# 09_Zynq_DDR.net
KiCad netlist of a schematic drawn in Altium Designer
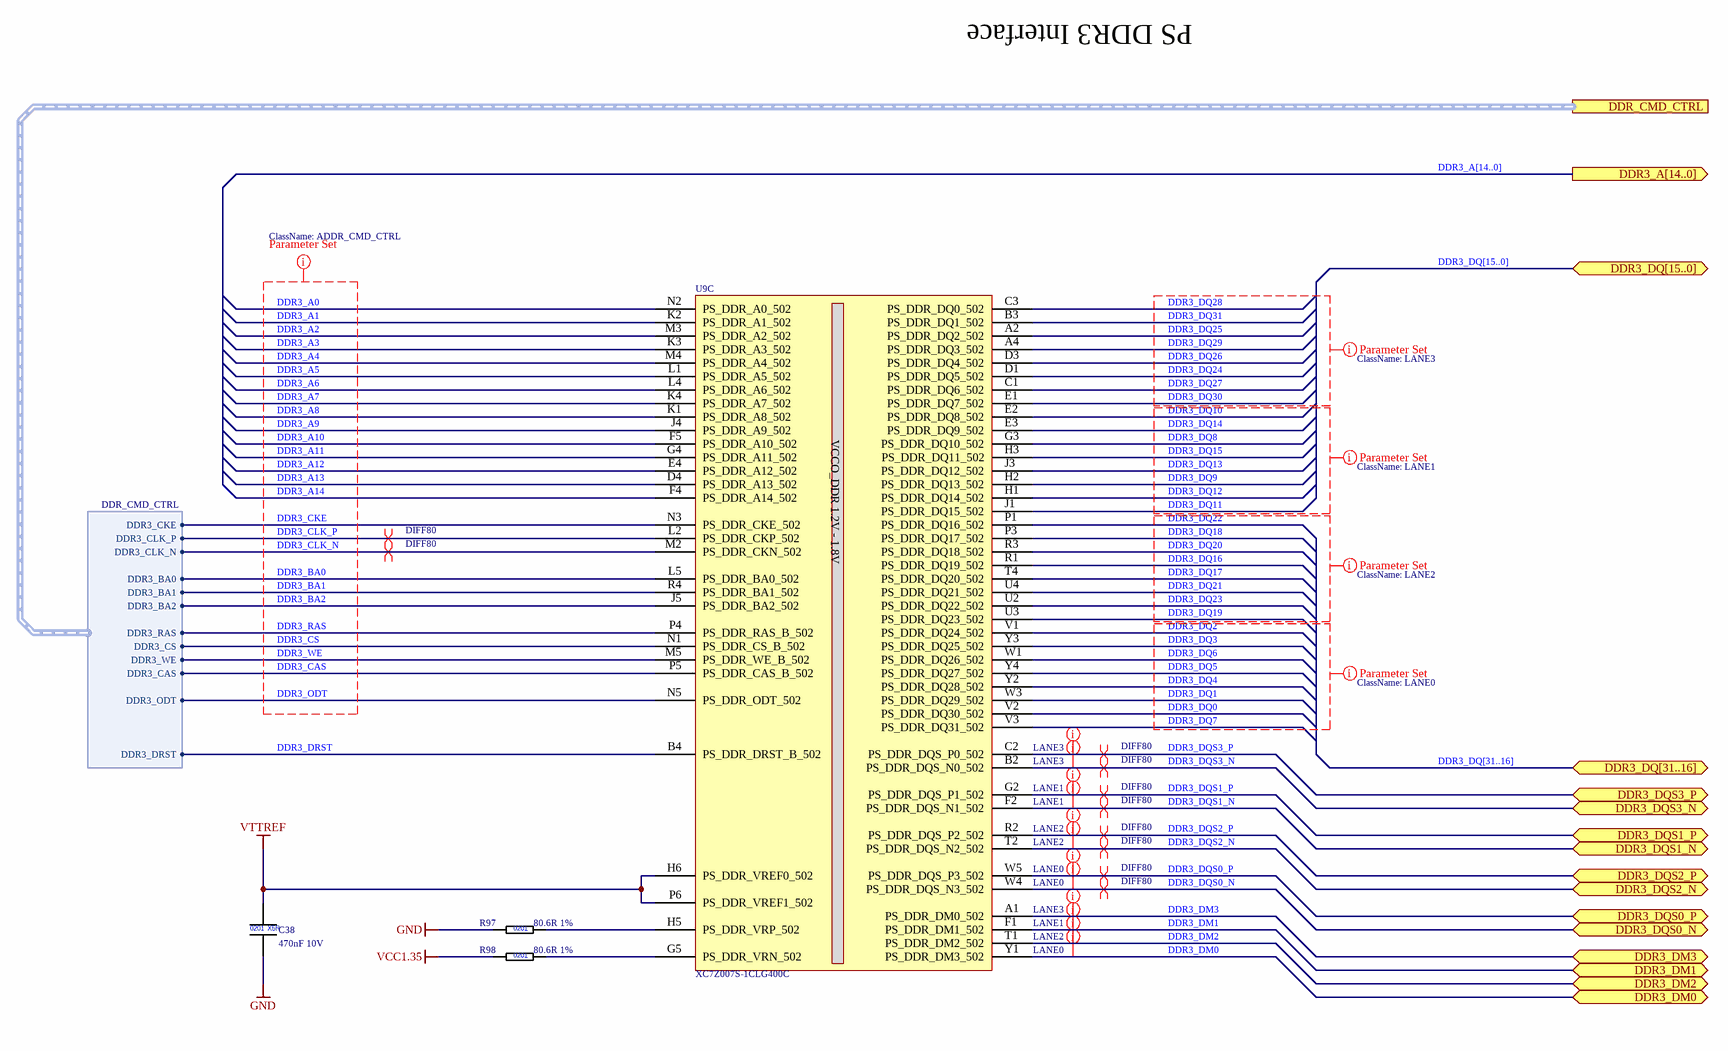
[diagram p0: 09_Zynq DDR.SchDoc]

(export (version "E")
  (design (tool "Eeschema 10.0.6"))
  (components
    (comp (ref "C38")
      (value "470nF 10V")
      (footprint "Zynq-Feather-HD:CAPC0603X03L")
      (description "Multilayer Ceramic Capacitors MLCC - SMD/SMT 0201 10VDC")
      (libsource (lib "Zynq-Feather-HD") (part "CAP_0201_470nF_10V"))
    )
    (comp (ref "R97")
      (value "80.6R 1%")
      (footprint "Zynq-Feather-HD:RESC0603X03L")
      (description "Thick Film Resistors - SMD 80.6R OHM 1%")
      (libsource (lib "Zynq-Feather-HD") (part "RES_0201_80.6R_1%"))
    )
    (comp (ref "R98")
      (value "80.6R 1%")
      (footprint "Zynq-Feather-HD:RESC0603X03L")
      (description "Thick Film Resistors - SMD 80.6R OHM 1%")
      (libsource (lib "Zynq-Feather-HD") (part "RES_0201_80.6R_1%"))
    )
    (comp (ref "U9")
      (value "XC7Z007S-1CLG400C")
      (footprint "Zynq-Feather-HD:BGA400C80P20X20_1700X1700X160")
      (description "XC7Z007S-1CLG400C_Processors - Application Specialised")
      (libsource (lib "Zynq-Feather-HD") (part "XC7Z007S-1CLG400C_Processors - Application Specialised"))
    )
  )
  (nets
    (net (code "2") (name "/DDR3_A0") (class "Default")
      (node (ref "U9") (pin "N2") (pinfunction "PS_DDR_A0_502_N2") (pintype "passive"))
    )
    (net (code "3") (name "/DDR3_A1") (class "Default")
      (node (ref "U9") (pin "K2") (pinfunction "PS_DDR_A1_502_K2") (pintype "passive"))
    )
    (net (code "4") (name "/DDR3_A2") (class "Default")
      (node (ref "U9") (pin "M3") (pinfunction "PS_DDR_A2_502_M3") (pintype "passive"))
    )
    (net (code "5") (name "/DDR3_A3") (class "Default")
      (node (ref "U9") (pin "K3") (pinfunction "PS_DDR_A3_502_K3") (pintype "passive"))
    )
    (net (code "6") (name "/DDR3_A4") (class "Default")
      (node (ref "U9") (pin "M4") (pinfunction "PS_DDR_A4_502_M4") (pintype "passive"))
    )
    (net (code "7") (name "/DDR3_A5") (class "Default")
      (node (ref "U9") (pin "L1") (pinfunction "PS_DDR_A5_502_L1") (pintype "passive"))
    )
    (net (code "8") (name "/DDR3_A6") (class "Default")
      (node (ref "U9") (pin "L4") (pinfunction "PS_DDR_A6_502_L4") (pintype "passive"))
    )
    (net (code "9") (name "/DDR3_A7") (class "Default")
      (node (ref "U9") (pin "K4") (pinfunction "PS_DDR_A7_502_K4") (pintype "passive"))
    )
    (net (code "10") (name "/DDR3_A8") (class "Default")
      (node (ref "U9") (pin "K1") (pinfunction "PS_DDR_A8_502_K1") (pintype "passive"))
    )
    (net (code "11") (name "/DDR3_A9") (class "Default")
      (node (ref "U9") (pin "J4") (pinfunction "PS_DDR_A9_502_J4") (pintype "passive"))
    )
    (net (code "12") (name "/DDR3_A10") (class "Default")
      (node (ref "U9") (pin "F5") (pinfunction "PS_DDR_A10_502_F5") (pintype "passive"))
    )
    (net (code "13") (name "/DDR3_A11") (class "Default")
      (node (ref "U9") (pin "G4") (pinfunction "PS_DDR_A11_502_G4") (pintype "passive"))
    )
    (net (code "14") (name "/DDR3_A12") (class "Default")
      (node (ref "U9") (pin "E4") (pinfunction "PS_DDR_A12_502_E4") (pintype "passive"))
    )
    (net (code "15") (name "/DDR3_A13") (class "Default")
      (node (ref "U9") (pin "D4") (pinfunction "PS_DDR_A13_502_D4") (pintype "passive"))
    )
    (net (code "16") (name "/DDR3_A14") (class "Default")
      (node (ref "U9") (pin "F4") (pinfunction "PS_DDR_A14_502_F4") (pintype "passive"))
    )
    (net (code "18") (name "/DDR3_BA0") (class "Default")
      (node (ref "U9") (pin "L5") (pinfunction "PS_DDR_BA0_502_L5") (pintype "passive"))
    )
    (net (code "19") (name "/DDR3_BA1") (class "Default")
      (node (ref "U9") (pin "R4") (pinfunction "PS_DDR_BA1_502_R4") (pintype "passive"))
    )
    (net (code "20") (name "/DDR3_BA2") (class "Default")
      (node (ref "U9") (pin "J5") (pinfunction "PS_DDR_BA2_502_J5") (pintype "passive"))
    )
    (net (code "21") (name "/DDR3_CAS") (class "Default")
      (node (ref "U9") (pin "P5") (pinfunction "PS_DDR_CAS_B_502_P5") (pintype "passive"))
    )
    (net (code "22") (name "/DDR3_CKE") (class "Default")
      (node (ref "U9") (pin "N3") (pinfunction "PS_DDR_CKE_502_N3") (pintype "passive"))
    )
    (net (code "23") (name "/DDR3_CLK_N") (class "Default")
      (node (ref "U9") (pin "M2") (pinfunction "PS_DDR_CKN_502_M2") (pintype "passive"))
    )
    (net (code "24") (name "/DDR3_CLK_P") (class "Default")
      (node (ref "U9") (pin "L2") (pinfunction "PS_DDR_CKP_502_L2") (pintype "passive"))
    )
    (net (code "25") (name "/DDR3_CS") (class "Default")
      (node (ref "U9") (pin "N1") (pinfunction "PS_DDR_CS_B_502_N1") (pintype "passive"))
    )
    (net (code "26") (name "/DDR3_DM0") (class "Default")
      (node (ref "U9") (pin "Y1") (pinfunction "PS_DDR_DM3_502_Y1") (pintype "passive"))
    )
    (net (code "27") (name "/DDR3_DM1") (class "Default")
      (node (ref "U9") (pin "F1") (pinfunction "PS_DDR_DM1_502_F1") (pintype "passive"))
    )
    (net (code "28") (name "/DDR3_DM2") (class "Default")
      (node (ref "U9") (pin "T1") (pinfunction "PS_DDR_DM2_502_T1") (pintype "passive"))
    )
    (net (code "29") (name "/DDR3_DM3") (class "Default")
      (node (ref "U9") (pin "A1") (pinfunction "PS_DDR_DM0_502_A1") (pintype "passive"))
    )
    (net (code "30") (name "/DDR3_DQ0") (class "Default")
      (node (ref "U9") (pin "V2") (pinfunction "PS_DDR_DQ30_502_V2") (pintype "passive"))
    )
    (net (code "31") (name "/DDR3_DQ1") (class "Default")
      (node (ref "U9") (pin "W3") (pinfunction "PS_DDR_DQ29_502_W3") (pintype "passive"))
    )
    (net (code "32") (name "/DDR3_DQ2") (class "Default")
      (node (ref "U9") (pin "V1") (pinfunction "PS_DDR_DQ24_502_V1") (pintype "passive"))
    )
    (net (code "33") (name "/DDR3_DQ3") (class "Default")
      (node (ref "U9") (pin "Y3") (pinfunction "PS_DDR_DQ25_502_Y3") (pintype "passive"))
    )
    (net (code "34") (name "/DDR3_DQ4") (class "Default")
      (node (ref "U9") (pin "Y2") (pinfunction "PS_DDR_DQ28_502_Y2") (pintype "passive"))
    )
    (net (code "35") (name "/DDR3_DQ5") (class "Default")
      (node (ref "U9") (pin "Y4") (pinfunction "PS_DDR_DQ27_502_Y4") (pintype "passive"))
    )
    (net (code "36") (name "/DDR3_DQ6") (class "Default")
      (node (ref "U9") (pin "W1") (pinfunction "PS_DDR_DQ26_502_W1") (pintype "passive"))
    )
    (net (code "37") (name "/DDR3_DQ7") (class "Default")
      (node (ref "U9") (pin "V3") (pinfunction "PS_DDR_DQ31_502_V3") (pintype "passive"))
    )
    (net (code "38") (name "/DDR3_DQ8") (class "Default")
      (node (ref "U9") (pin "G3") (pinfunction "PS_DDR_DQ10_502_G3") (pintype "passive"))
    )
    (net (code "39") (name "/DDR3_DQ9") (class "Default")
      (node (ref "U9") (pin "H2") (pinfunction "PS_DDR_DQ13_502_H2") (pintype "passive"))
    )
    (net (code "40") (name "/DDR3_DQ10") (class "Default")
      (node (ref "U9") (pin "E2") (pinfunction "PS_DDR_DQ8_502_E2") (pintype "passive"))
    )
    (net (code "41") (name "/DDR3_DQ11") (class "Default")
      (node (ref "U9") (pin "J1") (pinfunction "PS_DDR_DQ15_502_J1") (pintype "passive"))
    )
    (net (code "42") (name "/DDR3_DQ12") (class "Default")
      (node (ref "U9") (pin "H1") (pinfunction "PS_DDR_DQ14_502_H1") (pintype "passive"))
    )
    (net (code "43") (name "/DDR3_DQ13") (class "Default")
      (node (ref "U9") (pin "J3") (pinfunction "PS_DDR_DQ12_502_J3") (pintype "passive"))
    )
    (net (code "44") (name "/DDR3_DQ14") (class "Default")
      (node (ref "U9") (pin "E3") (pinfunction "PS_DDR_DQ9_502_E3") (pintype "passive"))
    )
    (net (code "45") (name "/DDR3_DQ15") (class "Default")
      (node (ref "U9") (pin "H3") (pinfunction "PS_DDR_DQ11_502_H3") (pintype "passive"))
    )
    (net (code "46") (name "/DDR3_DQ16") (class "Default")
      (node (ref "U9") (pin "R1") (pinfunction "PS_DDR_DQ19_502_R1") (pintype "passive"))
    )
    (net (code "47") (name "/DDR3_DQ17") (class "Default")
      (node (ref "U9") (pin "T4") (pinfunction "PS_DDR_DQ20_502_T4") (pintype "passive"))
    )
    (net (code "48") (name "/DDR3_DQ18") (class "Default")
      (node (ref "U9") (pin "P3") (pinfunction "PS_DDR_DQ17_502_P3") (pintype "passive"))
    )
    (net (code "49") (name "/DDR3_DQ19") (class "Default")
      (node (ref "U9") (pin "U3") (pinfunction "PS_DDR_DQ23_502_U3") (pintype "passive"))
    )
    (net (code "50") (name "/DDR3_DQ20") (class "Default")
      (node (ref "U9") (pin "R3") (pinfunction "PS_DDR_DQ18_502_R3") (pintype "passive"))
    )
    (net (code "51") (name "/DDR3_DQ21") (class "Default")
      (node (ref "U9") (pin "U4") (pinfunction "PS_DDR_DQ21_502_U4") (pintype "passive"))
    )
    (net (code "52") (name "/DDR3_DQ22") (class "Default")
      (node (ref "U9") (pin "P1") (pinfunction "PS_DDR_DQ16_502_P1") (pintype "passive"))
    )
    (net (code "53") (name "/DDR3_DQ23") (class "Default")
      (node (ref "U9") (pin "U2") (pinfunction "PS_DDR_DQ22_502_U2") (pintype "passive"))
    )
    (net (code "54") (name "/DDR3_DQ24") (class "Default")
      (node (ref "U9") (pin "D1") (pinfunction "PS_DDR_DQ5_502_D1") (pintype "passive"))
    )
    (net (code "55") (name "/DDR3_DQ25") (class "Default")
      (node (ref "U9") (pin "A2") (pinfunction "PS_DDR_DQ2_502_A2") (pintype "passive"))
    )
    (net (code "56") (name "/DDR3_DQ26") (class "Default")
      (node (ref "U9") (pin "D3") (pinfunction "PS_DDR_DQ4_502_D3") (pintype "passive"))
    )
    (net (code "57") (name "/DDR3_DQ27") (class "Default")
      (node (ref "U9") (pin "C1") (pinfunction "PS_DDR_DQ6_502_C1") (pintype "passive"))
    )
    (net (code "58") (name "/DDR3_DQ28") (class "Default")
      (node (ref "U9") (pin "C3") (pinfunction "PS_DDR_DQ0_502_C3") (pintype "passive"))
    )
    (net (code "59") (name "/DDR3_DQ29") (class "Default")
      (node (ref "U9") (pin "A4") (pinfunction "PS_DDR_DQ3_502_A4") (pintype "passive"))
    )
    (net (code "60") (name "/DDR3_DQ30") (class "Default")
      (node (ref "U9") (pin "E1") (pinfunction "PS_DDR_DQ7_502_E1") (pintype "passive"))
    )
    (net (code "61") (name "/DDR3_DQ31") (class "Default")
      (node (ref "U9") (pin "B3") (pinfunction "PS_DDR_DQ1_502_B3") (pintype "passive"))
    )
    (net (code "62") (name "/DDR3_DQS0_N") (class "Default")
      (node (ref "U9") (pin "W4") (pinfunction "PS_DDR_DQS_N3_502_W4") (pintype "passive"))
    )
    (net (code "63") (name "/DDR3_DQS0_P") (class "Default")
      (node (ref "U9") (pin "W5") (pinfunction "PS_DDR_DQS_P3_502_W5") (pintype "passive"))
    )
    (net (code "64") (name "/DDR3_DQS1_N") (class "Default")
      (node (ref "U9") (pin "F2") (pinfunction "PS_DDR_DQS_N1_502_F2") (pintype "passive"))
    )
    (net (code "65") (name "/DDR3_DQS1_P") (class "Default")
      (node (ref "U9") (pin "G2") (pinfunction "PS_DDR_DQS_P1_502_G2") (pintype "passive"))
    )
    (net (code "66") (name "/DDR3_DQS2_N") (class "Default")
      (node (ref "U9") (pin "T2") (pinfunction "PS_DDR_DQS_N2_502_T2") (pintype "passive"))
    )
    (net (code "67") (name "/DDR3_DQS2_P") (class "Default")
      (node (ref "U9") (pin "R2") (pinfunction "PS_DDR_DQS_P2_502_R2") (pintype "passive"))
    )
    (net (code "68") (name "/DDR3_DQS3_N") (class "Default")
      (node (ref "U9") (pin "B2") (pinfunction "PS_DDR_DQS_N0_502_B2") (pintype "passive"))
    )
    (net (code "69") (name "/DDR3_DQS3_P") (class "Default")
      (node (ref "U9") (pin "C2") (pinfunction "PS_DDR_DQS_P0_502_C2") (pintype "passive"))
    )
    (net (code "72") (name "/DDR3_DRST") (class "Default")
      (node (ref "U9") (pin "B4") (pinfunction "PS_DDR_DRST_B_502_B4") (pintype "passive"))
    )
    (net (code "73") (name "/DDR3_ODT") (class "Default")
      (node (ref "U9") (pin "N5") (pinfunction "PS_DDR_ODT_502_N5") (pintype "passive"))
    )
    (net (code "74") (name "/DDR3_RAS") (class "Default")
      (node (ref "U9") (pin "P4") (pinfunction "PS_DDR_RAS_B_502_P4") (pintype "passive"))
    )
    (net (code "75") (name "/DDR3_WE") (class "Default")
      (node (ref "U9") (pin "M5") (pinfunction "PS_DDR_WE_B_502_M5") (pintype "passive"))
    )
    (net (code "77") (name "GND") (class "Default")
      (node (ref "C38") (pin "2") (pinfunction "2_2") (pintype "passive"))
      (node (ref "R97") (pin "1") (pinfunction "1_1") (pintype "passive"))
    )
    (net (code "78") (name "Net-(U9C-PS_DDR_VRN_502)") (class "Default")
      (node (ref "R98") (pin "2") (pinfunction "2_2") (pintype "passive"))
      (node (ref "U9") (pin "G5") (pinfunction "PS_DDR_VRN_502_G5") (pintype "passive"))
    )
    (net (code "79") (name "Net-(U9C-PS_DDR_VRP_502)") (class "Default")
      (node (ref "R97") (pin "2") (pinfunction "2_2") (pintype "passive"))
      (node (ref "U9") (pin "H5") (pinfunction "PS_DDR_VRP_502_H5") (pintype "passive"))
    )
    (net (code "80") (name "VCC1.35") (class "Default")
      (node (ref "R98") (pin "1") (pinfunction "1_1") (pintype "passive"))
    )
    (net (code "81") (name "VTTREF") (class "Default")
      (node (ref "C38") (pin "1") (pinfunction "1_1") (pintype "passive"))
      (node (ref "U9") (pin "H6") (pinfunction "PS_DDR_VREF0_502_H6") (pintype "passive"))
      (node (ref "U9") (pin "P6") (pinfunction "PS_DDR_VREF1_502_P6") (pintype "passive"))
    )
  )
)
